# VT6212_Chipset.net
KiCad netlist of a schematic drawn in Altium Designer
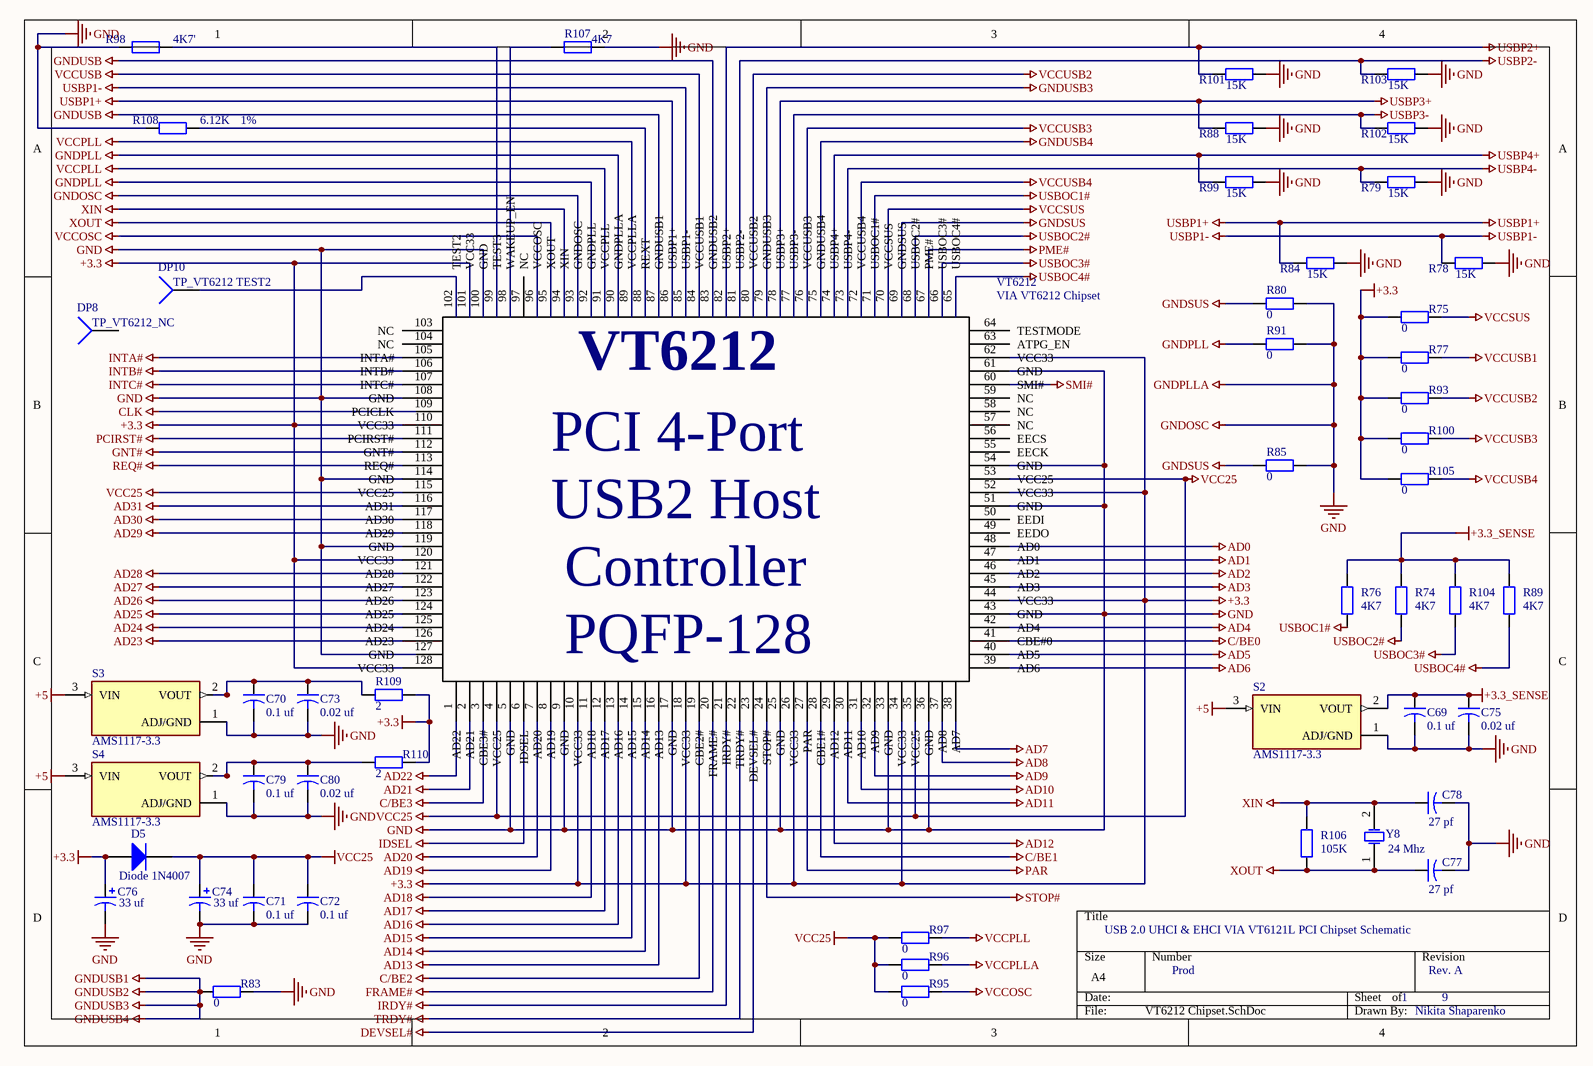
[diagram p0: VT6212 Chipset.SchDoc]

(export (version "E")
  (design (tool "Eeschema 10.0.6"))
  (components
    (comp (ref "C69")
      (value "0.1 uf")
      (footprint "CAPR5-4X5")
      (description "Capacitor")
      (fields (field (name "Comment") "Cap2") (field (name "PUBLISHER") "Altium Limited"))
      (libsource (lib "Miscellaneous Devices") (part "Cap2"))
    )
    (comp (ref "C70")
      (value "0.1 uf")
      (footprint "CAPR5-4X5")
      (description "Capacitor")
      (fields (field (name "Comment") "Cap2") (field (name "PUBLISHER") "Altium Limited"))
      (libsource (lib "Miscellaneous Devices") (part "Cap2"))
    )
    (comp (ref "C71")
      (value "0.1 uf")
      (footprint "CAPR5-4X5")
      (description "Capacitor")
      (fields (field (name "Comment") "Cap2") (field (name "PUBLISHER") "Altium Limited"))
      (libsource (lib "Miscellaneous Devices") (part "Cap2"))
    )
    (comp (ref "C72")
      (value "0.1 uf")
      (footprint "CAPR5-4X5")
      (description "Capacitor")
      (fields (field (name "Comment") "Cap2") (field (name "PUBLISHER") "Altium Limited"))
      (libsource (lib "Miscellaneous Devices") (part "Cap2"))
    )
    (comp (ref "C73")
      (value "0.02 uf")
      (footprint "CAPR5-4X5")
      (description "Capacitor")
      (fields (field (name "Comment") "Cap2") (field (name "PUBLISHER") "Altium Limited"))
      (libsource (lib "Miscellaneous Devices") (part "Cap2"))
    )
    (comp (ref "C74")
      (value "33 uf")
      (footprint "RAD-0.2")
      (description "Polarized Capacitor (Radial)")
      (fields (field (name "Comment") "Cap Pol1") (field (name "PUBLISHER") "Altium Limited"))
      (libsource (lib "Miscellaneous Devices") (part "Cap Pol1"))
    )
    (comp (ref "C75")
      (value "0.02 uf")
      (footprint "CAPR5-4X5")
      (description "Capacitor")
      (fields (field (name "Comment") "Cap2") (field (name "PUBLISHER") "Altium Limited"))
      (libsource (lib "Miscellaneous Devices") (part "Cap2"))
    )
    (comp (ref "C76")
      (value "33 uf")
      (footprint "RAD-0.2")
      (description "Polarized Capacitor (Radial)")
      (fields (field (name "Comment") "Cap Pol1") (field (name "PUBLISHER") "Altium Limited"))
      (libsource (lib "Miscellaneous Devices") (part "Cap Pol1"))
    )
    (comp (ref "C77")
      (value "27 pf")
      (footprint "CAPR5-4X5")
      (description "Capacitor")
      (fields (field (name "Comment") "Cap2") (field (name "PUBLISHER") "Altium Limited"))
      (libsource (lib "Miscellaneous Devices") (part "Cap2"))
    )
    (comp (ref "C78")
      (value "27 pf")
      (footprint "CAPR5-4X5")
      (description "Capacitor")
      (fields (field (name "Comment") "Cap2") (field (name "PUBLISHER") "Altium Limited"))
      (libsource (lib "Miscellaneous Devices") (part "Cap2"))
    )
    (comp (ref "C79")
      (value "0.1 uf")
      (footprint "CAPR5-4X5")
      (description "Capacitor")
      (fields (field (name "Comment") "Cap2") (field (name "PUBLISHER") "Altium Limited"))
      (libsource (lib "Miscellaneous Devices") (part "Cap2"))
    )
    (comp (ref "C80")
      (value "0.02 uf")
      (footprint "CAPR5-4X5")
      (description "Capacitor")
      (fields (field (name "Comment") "Cap2") (field (name "PUBLISHER") "Altium Limited"))
      (libsource (lib "Miscellaneous Devices") (part "Cap2"))
    )
    (comp (ref "D5")
      (value "Diode 1N4007")
      (footprint "DO-41")
      (description "1 Amp General Purpose Rectifier")
      (fields (field (name "PUBLISHER") "Altium Limited"))
      (libsource (lib "Miscellaneous Devices") (part "Diode 1N4007"))
    )
    (comp (ref "DP8")
      (value "TP_VT6212_NC")
      (footprint "PIN1")
      (description "Socket")
      (fields (field (name "PUBLISHER") "Altium Limited"))
      (libsource (lib "Miscellaneous Connectors") (part "Socket"))
    )
    (comp (ref "DP10")
      (value "TP_VT6212 TEST2")
      (footprint "PIN1")
      (description "Socket")
      (fields (field (name "PUBLISHER") "Altium Limited"))
      (libsource (lib "Miscellaneous Connectors") (part "Socket"))
    )
    (comp (ref "R74")
      (value "4K7")
      (footprint "AXIAL-0.4")
      (description "Resistor")
      (fields (field (name "Comment") "Res2") (field (name "PUBLISHER") "Altium Limited"))
      (libsource (lib "") (part "Res2_2"))
    )
    (comp (ref "R75")
      (value "0")
      (footprint "AXIAL-0.4")
      (description "Resistor")
      (fields (field (name "Comment") "Res2") (field (name "PUBLISHER") "Altium Limited"))
      (libsource (lib "Miscellaneous Devices") (part "Res2"))
    )
    (comp (ref "R76")
      (value "4K7")
      (footprint "AXIAL-0.4")
      (description "Resistor")
      (fields (field (name "Comment") "Res2") (field (name "PUBLISHER") "Altium Limited"))
      (libsource (lib "") (part "Res2_2"))
    )
    (comp (ref "R77")
      (value "0")
      (footprint "AXIAL-0.4")
      (description "Resistor")
      (fields (field (name "Comment") "Res2") (field (name "PUBLISHER") "Altium Limited"))
      (libsource (lib "Miscellaneous Devices") (part "Res2"))
    )
    (comp (ref "R78")
      (value "15K")
      (footprint "AXIAL-0.4")
      (description "Resistor")
      (fields (field (name "Comment") "Res2") (field (name "PUBLISHER") "Altium Limited"))
      (libsource (lib "Miscellaneous Devices") (part "Res2"))
    )
    (comp (ref "R79")
      (value "15K")
      (footprint "AXIAL-0.4")
      (description "Resistor")
      (fields (field (name "Comment") "Res2") (field (name "PUBLISHER") "Altium Limited"))
      (libsource (lib "Miscellaneous Devices") (part "Res2"))
    )
    (comp (ref "R80")
      (value "0")
      (footprint "AXIAL-0.4")
      (description "Resistor")
      (fields (field (name "Comment") "Res2") (field (name "PUBLISHER") "Altium Limited"))
      (libsource (lib "") (part "Res2_1"))
    )
    (comp (ref "R83")
      (value "0")
      (footprint "AXIAL-0.4")
      (description "Resistor")
      (fields (field (name "Comment") "Res2") (field (name "PUBLISHER") "Altium Limited"))
      (libsource (lib "Miscellaneous Devices") (part "Res2"))
    )
    (comp (ref "R84")
      (value "15K")
      (footprint "AXIAL-0.4")
      (description "Resistor")
      (fields (field (name "Comment") "Res2") (field (name "PUBLISHER") "Altium Limited"))
      (libsource (lib "Miscellaneous Devices") (part "Res2"))
    )
    (comp (ref "R85")
      (value "0")
      (footprint "AXIAL-0.4")
      (description "Resistor")
      (fields (field (name "Comment") "Res2") (field (name "PUBLISHER") "Altium Limited"))
      (libsource (lib "") (part "Res2_1"))
    )
    (comp (ref "R88")
      (value "15K")
      (footprint "AXIAL-0.4")
      (description "Resistor")
      (fields (field (name "Comment") "Res2") (field (name "PUBLISHER") "Altium Limited"))
      (libsource (lib "Miscellaneous Devices") (part "Res2"))
    )
    (comp (ref "R89")
      (value "4K7")
      (footprint "AXIAL-0.4")
      (description "Resistor")
      (fields (field (name "Comment") "Res2") (field (name "PUBLISHER") "Altium Limited"))
      (libsource (lib "") (part "Res2_2"))
    )
    (comp (ref "R91")
      (value "0")
      (footprint "AXIAL-0.4")
      (description "Resistor")
      (fields (field (name "Comment") "Res2") (field (name "PUBLISHER") "Altium Limited"))
      (libsource (lib "") (part "Res2_1"))
    )
    (comp (ref "R93")
      (value "0")
      (footprint "AXIAL-0.4")
      (description "Resistor")
      (fields (field (name "Comment") "Res2") (field (name "PUBLISHER") "Altium Limited"))
      (libsource (lib "Miscellaneous Devices") (part "Res2"))
    )
    (comp (ref "R95")
      (value "0")
      (footprint "AXIAL-0.4")
      (description "Resistor")
      (fields (field (name "Comment") "Res2") (field (name "PUBLISHER") "Altium Limited"))
      (libsource (lib "Miscellaneous Devices") (part "Res2"))
    )
    (comp (ref "R96")
      (value "0")
      (footprint "AXIAL-0.4")
      (description "Resistor")
      (fields (field (name "Comment") "Res2") (field (name "PUBLISHER") "Altium Limited"))
      (libsource (lib "Miscellaneous Devices") (part "Res2"))
    )
    (comp (ref "R97")
      (value "0")
      (footprint "AXIAL-0.4")
      (description "Resistor")
      (fields (field (name "Comment") "Res2") (field (name "PUBLISHER") "Altium Limited"))
      (libsource (lib "Miscellaneous Devices") (part "Res2"))
    )
    (comp (ref "R98")
      (value "4K7'")
      (footprint "AXIAL-0.4")
      (description "Resistor")
      (fields (field (name "PUBLISHER") "Altium Limited"))
      (libsource (lib "") (part "Res2_1"))
    )
    (comp (ref "R99")
      (value "15K")
      (footprint "AXIAL-0.4")
      (description "Resistor")
      (fields (field (name "Comment") "Res2") (field (name "PUBLISHER") "Altium Limited"))
      (libsource (lib "Miscellaneous Devices") (part "Res2"))
    )
    (comp (ref "R100")
      (value "0")
      (footprint "AXIAL-0.4")
      (description "Resistor")
      (fields (field (name "Comment") "Res2") (field (name "PUBLISHER") "Altium Limited"))
      (libsource (lib "Miscellaneous Devices") (part "Res2"))
    )
    (comp (ref "R101")
      (value "15K")
      (footprint "AXIAL-0.4")
      (description "Resistor")
      (fields (field (name "Comment") "Res2") (field (name "PUBLISHER") "Altium Limited"))
      (libsource (lib "Miscellaneous Devices") (part "Res2"))
    )
    (comp (ref "R102")
      (value "15K")
      (footprint "AXIAL-0.4")
      (description "Resistor")
      (fields (field (name "Comment") "Res2") (field (name "PUBLISHER") "Altium Limited"))
      (libsource (lib "Miscellaneous Devices") (part "Res2"))
    )
    (comp (ref "R103")
      (value "15K")
      (footprint "AXIAL-0.4")
      (description "Resistor")
      (fields (field (name "Comment") "Res2") (field (name "PUBLISHER") "Altium Limited"))
      (libsource (lib "Miscellaneous Devices") (part "Res2"))
    )
    (comp (ref "R104")
      (value "4K7")
      (footprint "AXIAL-0.4")
      (description "Resistor")
      (fields (field (name "Comment") "Res2") (field (name "PUBLISHER") "Altium Limited"))
      (libsource (lib "") (part "Res2_2"))
    )
    (comp (ref "R105")
      (value "0")
      (footprint "AXIAL-0.4")
      (description "Resistor")
      (fields (field (name "Comment") "Res2") (field (name "PUBLISHER") "Altium Limited"))
      (libsource (lib "Miscellaneous Devices") (part "Res2"))
    )
    (comp (ref "R106")
      (value "105K")
      (footprint "AXIAL-0.4")
      (description "Resistor")
      (fields (field (name "Comment") "Res2") (field (name "PUBLISHER") "Altium Limited"))
      (libsource (lib "") (part "Res2_2"))
    )
    (comp (ref "R107")
      (value "4K7")
      (footprint "AXIAL-0.4")
      (description "Resistor")
      (fields (field (name "Comment") "Res2") (field (name "PUBLISHER") "Altium Limited"))
      (libsource (lib "Miscellaneous Devices") (part "Res2"))
    )
    (comp (ref "R108")
      (value "1%")
      (footprint "AXIAL-0.4")
      (description "Resistor")
      (fields (field (name "ALTIUM_VALUE") "6.12K") (field (name "PUBLISHER") "Altium Limited"))
      (libsource (lib "") (part "Res2_1"))
    )
    (comp (ref "R109")
      (value "2")
      (footprint "AXIAL-0.4")
      (description "Resistor")
      (fields (field (name "Comment") "Res2") (field (name "PUBLISHER") "Altium Limited"))
      (libsource (lib "") (part "Res2_1"))
    )
    (comp (ref "R110")
      (value "2")
      (footprint "AXIAL-0.4")
      (description "Resistor")
      (fields (field (name "Comment") "Res2") (field (name "PUBLISHER") "Altium Limited"))
      (libsource (lib "Miscellaneous Devices") (part "Res2"))
    )
    (comp (ref "S2")
      (value "AMS1117-3.3")
      (footprint "SOT229P700X180-4N")
      (description "Sot223/Pkg 1-Amp 3.3-Volt Low Drop Out Voltage Regulatator")
      (fields (field (name "MF") "Advanced Monolithic Systems"))
      (libsource (lib "AMS1117-3.3") (part "AMS1117-3.3"))
    )
    (comp (ref "S3")
      (value "AMS1117-3.3")
      (footprint "SOT229P700X180-4N")
      (description "Sot223/Pkg 1-Amp 3.3-Volt Low Drop Out Voltage Regulatator")
      (fields (field (name "MF") "Advanced Monolithic Systems"))
      (libsource (lib "AMS1117-3.3") (part "AMS1117-3.3"))
    )
    (comp (ref "S4")
      (value "AMS1117-3.3")
      (footprint "SOT229P700X180-4N")
      (description "Sot223/Pkg 1-Amp 3.3-Volt Low Drop Out Voltage Regulatator")
      (fields (field (name "MF") "Advanced Monolithic Systems"))
      (libsource (lib "AMS1117-3.3") (part "AMS1117-3.3"))
    )
    (comp (ref "VT6212")
      (value "VIA VT6212 Chipset")
      (footprint "NXP LQFP-144 SOT486-1")
      (description "VT6212 PCI 4-Port USB2 Host Controller PQFP-128")
      (libsource (lib "VIA VT6212") (part "VT6212"))
    )
    (comp (ref "Y8")
      (value "24 Mhz")
      (footprint "R38")
      (description "Crystal Oscillator")
      (fields (field (name "PUBLISHER") "Altium Limited"))
      (libsource (lib "Miscellaneous Devices") (part "XTAL"))
    )
  )
  (nets
    (net (code "1") (name "+3.3") (class "Default")
      (node (ref "C76") (pin "1") (pinfunction "1_1") (pintype "passive"))
      (node (ref "D5") (pin "1") (pinfunction "A_1") (pintype "passive"))
      (node (ref "R100") (pin "2") (pinfunction "2_2") (pintype "passive"))
      (node (ref "R105") (pin "2") (pinfunction "2_2") (pintype "passive"))
      (node (ref "R109") (pin "2") (pinfunction "2_2") (pintype "passive"))
      (node (ref "R110") (pin "1") (pinfunction "1_1") (pintype "passive"))
      (node (ref "R75") (pin "2") (pinfunction "2_2") (pintype "passive"))
      (node (ref "R77") (pin "2") (pinfunction "2_2") (pintype "passive"))
      (node (ref "R93") (pin "2") (pinfunction "2_2") (pintype "passive"))
      (node (ref "VT6212") (pin "101") (pinfunction "VCC33_101") (pintype "passive"))
    )
    (net (code "2") (name "+3.3_SENSE") (class "Default")
      (node (ref "C69") (pin "1") (pinfunction "1_1") (pintype "passive"))
      (node (ref "C75") (pin "1") (pinfunction "1_1") (pintype "passive"))
      (node (ref "R104") (pin "2") (pinfunction "2_2") (pintype "passive"))
      (node (ref "R74") (pin "2") (pinfunction "2_2") (pintype "passive"))
      (node (ref "R76") (pin "2") (pinfunction "2_2") (pintype "passive"))
      (node (ref "R89") (pin "2") (pinfunction "2_2") (pintype "passive"))
      (node (ref "S2") (pin "2") (pinfunction "VOUT_2") (pintype "output"))
    )
    (net (code "3") (name "+5") (class "Default")
      (node (ref "S2") (pin "3") (pinfunction "VIN_3") (pintype "input"))
      (node (ref "S3") (pin "3") (pinfunction "VIN_3") (pintype "input"))
      (node (ref "S4") (pin "3") (pinfunction "VIN_3") (pintype "input"))
    )
    (net (code "43") (name "GND") (class "Default")
      (node (ref "C69") (pin "2") (pinfunction "2_2") (pintype "passive"))
      (node (ref "C70") (pin "2") (pinfunction "2_2") (pintype "passive"))
      (node (ref "C71") (pin "2") (pinfunction "2_2") (pintype "passive"))
      (node (ref "C72") (pin "2") (pinfunction "2_2") (pintype "passive"))
      (node (ref "C73") (pin "2") (pinfunction "2_2") (pintype "passive"))
      (node (ref "C74") (pin "2") (pinfunction "2_2") (pintype "passive"))
      (node (ref "C75") (pin "2") (pinfunction "2_2") (pintype "passive"))
      (node (ref "C76") (pin "2") (pinfunction "2_2") (pintype "passive"))
      (node (ref "C77") (pin "2") (pinfunction "2_2") (pintype "passive"))
      (node (ref "C78") (pin "2") (pinfunction "2_2") (pintype "passive"))
      (node (ref "C79") (pin "2") (pinfunction "2_2") (pintype "passive"))
      (node (ref "C80") (pin "2") (pinfunction "2_2") (pintype "passive"))
      (node (ref "R101") (pin "1") (pinfunction "1_1") (pintype "passive"))
      (node (ref "R102") (pin "1") (pinfunction "1_1") (pintype "passive"))
      (node (ref "R103") (pin "1") (pinfunction "1_1") (pintype "passive"))
      (node (ref "R107") (pin "1") (pinfunction "1_1") (pintype "passive"))
      (node (ref "R108") (pin "1") (pinfunction "1_1") (pintype "passive"))
      (node (ref "R78") (pin "1") (pinfunction "1_1") (pintype "passive"))
      (node (ref "R79") (pin "1") (pinfunction "1_1") (pintype "passive"))
      (node (ref "R80") (pin "2") (pinfunction "2_2") (pintype "passive"))
      (node (ref "R83") (pin "1") (pinfunction "1_1") (pintype "passive"))
      (node (ref "R84") (pin "1") (pinfunction "1_1") (pintype "passive"))
      (node (ref "R85") (pin "2") (pinfunction "2_2") (pintype "passive"))
      (node (ref "R88") (pin "1") (pinfunction "1_1") (pintype "passive"))
      (node (ref "R91") (pin "2") (pinfunction "2_2") (pintype "passive"))
      (node (ref "R98") (pin "1") (pinfunction "1_1") (pintype "passive"))
      (node (ref "R99") (pin "1") (pinfunction "1_1") (pintype "passive"))
      (node (ref "S2") (pin "1") (pinfunction "ADJ/GND_1") (pintype "power_in"))
      (node (ref "S3") (pin "1") (pinfunction "ADJ/GND_1") (pintype "power_in"))
      (node (ref "S4") (pin "1") (pinfunction "ADJ/GND_1") (pintype "power_in"))
      (node (ref "VT6212") (pin "100") (pinfunction "GND_100") (pintype "passive"))
      (node (ref "VT6212") (pin "93") (pinfunction "GNDOSC_93") (pintype "passive"))
    )
    (net (code "44") (name "GNDPLL") (class "Default")
      (node (ref "R91") (pin "1") (pinfunction "1_1") (pintype "passive"))
      (node (ref "VT6212") (pin "90") (pinfunction "GNDPLLA_90") (pintype "passive"))
      (node (ref "VT6212") (pin "92") (pinfunction "GNDPLL_92") (pintype "passive"))
    )
    (net (code "45") (name "GNDSUS") (class "Default")
      (node (ref "R80") (pin "1") (pinfunction "1_1") (pintype "passive"))
      (node (ref "R85") (pin "1") (pinfunction "1_1") (pintype "passive"))
      (node (ref "VT6212") (pin "69") (pinfunction "GNDSUS_69") (pintype "passive"))
    )
    (net (code "46") (name "GNDUSB") (class "Default")
      (node (ref "VT6212") (pin "83") (pinfunction "GNDUSB2_83") (pintype "passive"))
      (node (ref "VT6212") (pin "87") (pinfunction "GNDUSB1_87") (pintype "passive"))
    )
    (net (code "47") (name "GNDUSB1") (class "Default")
      (node (ref "R83") (pin "2") (pinfunction "2_2") (pintype "passive"))
      (node (ref "VT6212") (pin "75") (pinfunction "GNDUSB4_75") (pintype "passive"))
      (node (ref "VT6212") (pin "79") (pinfunction "GNDUSB3_79") (pintype "passive"))
    )
    (net (code "54") (name "Net-(S3-VOUT)") (class "Default")
      (node (ref "C70") (pin "1") (pinfunction "1_1") (pintype "passive"))
      (node (ref "C73") (pin "1") (pinfunction "1_1") (pintype "passive"))
      (node (ref "R109") (pin "1") (pinfunction "1_1") (pintype "passive"))
      (node (ref "S3") (pin "2") (pinfunction "VOUT_2") (pintype "output"))
    )
    (net (code "55") (name "Net-(S4-VOUT)") (class "Default")
      (node (ref "C79") (pin "1") (pinfunction "1_1") (pintype "passive"))
      (node (ref "C80") (pin "1") (pinfunction "1_1") (pintype "passive"))
      (node (ref "R110") (pin "2") (pinfunction "2_2") (pintype "passive"))
      (node (ref "S4") (pin "2") (pinfunction "VOUT_2") (pintype "output"))
    )
    (net (code "56") (name "Net-(VT6212-REXT)") (class "Default")
      (node (ref "R108") (pin "2") (pinfunction "2_2") (pintype "passive"))
      (node (ref "VT6212") (pin "88") (pinfunction "REXT_88") (pintype "passive"))
    )
    (net (code "57") (name "Net-(VT6212-TEST2)") (class "Default")
      (node (ref "DP10") (pin "1") (pinfunction "1_1") (pintype "passive"))
      (node (ref "VT6212") (pin "102") (pinfunction "TEST2_102") (pintype "passive"))
    )
    (net (code "58") (name "Net-(VT6212-TEST3)") (class "Default")
      (node (ref "R98") (pin "2") (pinfunction "2_2") (pintype "passive"))
      (node (ref "VT6212") (pin "99") (pinfunction "TEST3_99") (pintype "passive"))
    )
    (net (code "59") (name "Net-(VT6212-WAKEUP_EN)") (class "Default")
      (node (ref "R107") (pin "2") (pinfunction "2_2") (pintype "passive"))
      (node (ref "VT6212") (pin "98") (pinfunction "WAKEUP_EN_98") (pintype "passive"))
    )
    (net (code "62") (name "PME#") (class "Default")
      (node (ref "VT6212") (pin "67") (pinfunction "PME#_67") (pintype "passive"))
    )
    (net (code "67") (name "USBOC1#") (class "Default")
      (node (ref "R76") (pin "1") (pinfunction "1_1") (pintype "passive"))
      (node (ref "VT6212") (pin "71") (pinfunction "USBOC1#_71") (pintype "passive"))
    )
    (net (code "68") (name "USBOC2#") (class "Default")
      (node (ref "R74") (pin "1") (pinfunction "1_1") (pintype "passive"))
      (node (ref "VT6212") (pin "68") (pinfunction "USBOC2#_68") (pintype "passive"))
    )
    (net (code "69") (name "USBOC3#") (class "Default")
      (node (ref "R104") (pin "1") (pinfunction "1_1") (pintype "passive"))
      (node (ref "VT6212") (pin "66") (pinfunction "USBOC3#_66") (pintype "passive"))
    )
    (net (code "70") (name "USBOC4#") (class "Default")
      (node (ref "R89") (pin "1") (pinfunction "1_1") (pintype "passive"))
      (node (ref "VT6212") (pin "65") (pinfunction "USBOC4#_65") (pintype "passive"))
    )
    (net (code "71") (name "USBP1+") (class "Default")
      (node (ref "R84") (pin "2") (pinfunction "2_2") (pintype "passive"))
      (node (ref "VT6212") (pin "86") (pinfunction "USBP1+_86") (pintype "passive"))
    )
    (net (code "72") (name "USBP1-") (class "Default")
      (node (ref "R78") (pin "2") (pinfunction "2_2") (pintype "passive"))
      (node (ref "VT6212") (pin "85") (pinfunction "USBP1-_85") (pintype "passive"))
    )
    (net (code "73") (name "USBP2+") (class "Default")
      (node (ref "R101") (pin "2") (pinfunction "2_2") (pintype "passive"))
      (node (ref "VT6212") (pin "82") (pinfunction "USBP2+_82") (pintype "passive"))
    )
    (net (code "74") (name "USBP2-") (class "Default")
      (node (ref "R103") (pin "2") (pinfunction "2_2") (pintype "passive"))
      (node (ref "VT6212") (pin "81") (pinfunction "USBP2-_81") (pintype "passive"))
    )
    (net (code "75") (name "USBP3+") (class "Default")
      (node (ref "R88") (pin "2") (pinfunction "2_2") (pintype "passive"))
      (node (ref "VT6212") (pin "78") (pinfunction "USBP3+_78") (pintype "passive"))
    )
    (net (code "76") (name "USBP3-") (class "Default")
      (node (ref "R102") (pin "2") (pinfunction "2_2") (pintype "passive"))
      (node (ref "VT6212") (pin "77") (pinfunction "USBP3-_77") (pintype "passive"))
    )
    (net (code "77") (name "USBP4+") (class "Default")
      (node (ref "R99") (pin "2") (pinfunction "2_2") (pintype "passive"))
      (node (ref "VT6212") (pin "74") (pinfunction "USBP4+_74") (pintype "passive"))
    )
    (net (code "78") (name "USBP4-") (class "Default")
      (node (ref "R79") (pin "2") (pinfunction "2_2") (pintype "passive"))
      (node (ref "VT6212") (pin "73") (pinfunction "USBP4-_73") (pintype "passive"))
    )
    (net (code "79") (name "VCC25") (class "Default")
      (node (ref "C71") (pin "1") (pinfunction "1_1") (pintype "passive"))
      (node (ref "C72") (pin "1") (pinfunction "1_1") (pintype "passive"))
      (node (ref "C74") (pin "1") (pinfunction "1_1") (pintype "passive"))
      (node (ref "D5") (pin "2") (pinfunction "K_2") (pintype "passive"))
      (node (ref "R95") (pin "2") (pinfunction "2_2") (pintype "passive"))
      (node (ref "R96") (pin "2") (pinfunction "2_2") (pintype "passive"))
      (node (ref "R97") (pin "2") (pinfunction "2_2") (pintype "passive"))
    )
    (net (code "80") (name "VCCOSC") (class "Default")
      (node (ref "R95") (pin "1") (pinfunction "1_1") (pintype "passive"))
      (node (ref "VT6212") (pin "96") (pinfunction "VCCOSC_96") (pintype "passive"))
    )
    (net (code "81") (name "VCCPLL") (class "Default")
      (node (ref "R97") (pin "1") (pinfunction "1_1") (pintype "passive"))
      (node (ref "VT6212") (pin "89") (pinfunction "VCCPLLA_89") (pintype "passive"))
      (node (ref "VT6212") (pin "91") (pinfunction "VCCPLL_91") (pintype "passive"))
    )
    (net (code "82") (name "VCCPLLA") (class "Default")
      (node (ref "R96") (pin "1") (pinfunction "1_1") (pintype "passive"))
    )
    (net (code "83") (name "VCCSUS") (class "Default")
      (node (ref "R75") (pin "1") (pinfunction "1_1") (pintype "passive"))
      (node (ref "VT6212") (pin "70") (pinfunction "VCCSUS_70") (pintype "passive"))
    )
    (net (code "84") (name "VCCUSB") (class "Default")
      (node (ref "VT6212") (pin "84") (pinfunction "VCCUSB1_84") (pintype "passive"))
    )
    (net (code "85") (name "VCCUSB1") (class "Default")
      (node (ref "R77") (pin "1") (pinfunction "1_1") (pintype "passive"))
    )
    (net (code "86") (name "VCCUSB2") (class "Default")
      (node (ref "R93") (pin "1") (pinfunction "1_1") (pintype "passive"))
      (node (ref "VT6212") (pin "80") (pinfunction "VCCUSB2_80") (pintype "passive"))
    )
    (net (code "87") (name "VCCUSB3") (class "Default")
      (node (ref "R100") (pin "1") (pinfunction "1_1") (pintype "passive"))
      (node (ref "VT6212") (pin "76") (pinfunction "VCCUSB3_76") (pintype "passive"))
    )
    (net (code "88") (name "VCCUSB4") (class "Default")
      (node (ref "R105") (pin "1") (pinfunction "1_1") (pintype "passive"))
      (node (ref "VT6212") (pin "72") (pinfunction "VCCUSB4_72") (pintype "passive"))
    )
    (net (code "89") (name "XIN") (class "Default")
      (node (ref "C78") (pin "1") (pinfunction "1_1") (pintype "passive"))
      (node (ref "R106") (pin "2") (pinfunction "2_2") (pintype "passive"))
      (node (ref "VT6212") (pin "94") (pinfunction "XIN_94") (pintype "passive"))
      (node (ref "Y8") (pin "2") (pinfunction "OSC2_2") (pintype "passive"))
    )
    (net (code "90") (name "XOUT") (class "Default")
      (node (ref "C77") (pin "1") (pinfunction "1_1") (pintype "passive"))
      (node (ref "R106") (pin "1") (pinfunction "1_1") (pintype "passive"))
      (node (ref "VT6212") (pin "95") (pinfunction "XOUT_95") (pintype "passive"))
      (node (ref "Y8") (pin "1") (pinfunction "OSC1_1") (pintype "passive"))
    )
    (net (code "91") (name "unconnected-(DP8-Pad1)") (class "Default")
      (node (ref "DP8") (pin "1") (pinfunction "1_1") (pintype "passive"))
    )
    (net (code "92") (name "unconnected-(VT6212-AD0-Pad48)") (class "Default")
      (node (ref "VT6212") (pin "48") (pinfunction "AD0_48") (pintype "passive"))
    )
    (net (code "93") (name "unconnected-(VT6212-AD1-Pad47)") (class "Default")
      (node (ref "VT6212") (pin "47") (pinfunction "AD1_47") (pintype "passive"))
    )
    (net (code "94") (name "unconnected-(VT6212-AD2-Pad46)") (class "Default")
      (node (ref "VT6212") (pin "46") (pinfunction "AD2_46") (pintype "passive"))
    )
    (net (code "95") (name "unconnected-(VT6212-AD3-Pad45)") (class "Default")
      (node (ref "VT6212") (pin "45") (pinfunction "AD3_45") (pintype "passive"))
    )
    (net (code "96") (name "unconnected-(VT6212-AD4-Pad42)") (class "Default")
      (node (ref "VT6212") (pin "42") (pinfunction "AD4_42") (pintype "passive"))
    )
    (net (code "97") (name "unconnected-(VT6212-AD5-Pad40)") (class "Default")
      (node (ref "VT6212") (pin "40") (pinfunction "AD5_40") (pintype "passive"))
    )
    (net (code "98") (name "unconnected-(VT6212-AD6-Pad39)") (class "Default")
      (node (ref "VT6212") (pin "39") (pinfunction "AD6_39") (pintype "passive"))
    )
    (net (code "99") (name "unconnected-(VT6212-AD7-Pad38)") (class "Default")
      (node (ref "VT6212") (pin "38") (pinfunction "AD7_38") (pintype "passive"))
    )
    (net (code "100") (name "unconnected-(VT6212-AD8-Pad37)") (class "Default")
      (node (ref "VT6212") (pin "37") (pinfunction "AD8_37") (pintype "passive"))
    )
    (net (code "101") (name "unconnected-(VT6212-AD9-Pad32)") (class "Default")
      (node (ref "VT6212") (pin "32") (pinfunction "AD9_32") (pintype "passive"))
    )
    (net (code "102") (name "unconnected-(VT6212-AD10-Pad31)") (class "Default")
      (node (ref "VT6212") (pin "31") (pinfunction "AD10_31") (pintype "passive"))
    )
    (net (code "103") (name "unconnected-(VT6212-AD11-Pad30)") (class "Default")
      (node (ref "VT6212") (pin "30") (pinfunction "AD11_30") (pintype "passive"))
    )
    (net (code "104") (name "unconnected-(VT6212-AD12-Pad29)") (class "Default")
      (node (ref "VT6212") (pin "29") (pinfunction "AD12_29") (pintype "passive"))
    )
    (net (code "105") (name "unconnected-(VT6212-AD13-Pad16)") (class "Default")
      (node (ref "VT6212") (pin "16") (pinfunction "AD13_16") (pintype "passive"))
    )
    (net (code "106") (name "unconnected-(VT6212-AD14-Pad15)") (class "Default")
      (node (ref "VT6212") (pin "15") (pinfunction "AD14_15") (pintype "passive"))
    )
    (net (code "107") (name "unconnected-(VT6212-AD15-Pad14)") (class "Default")
      (node (ref "VT6212") (pin "14") (pinfunction "AD15_14") (pintype "passive"))
    )
    (net (code "108") (name "unconnected-(VT6212-AD16-Pad13)") (class "Default")
      (node (ref "VT6212") (pin "13") (pinfunction "AD16_13") (pintype "passive"))
    )
    (net (code "109") (name "unconnected-(VT6212-AD17-Pad12)") (class "Default")
      (node (ref "VT6212") (pin "12") (pinfunction "AD17_12") (pintype "passive"))
    )
    (net (code "110") (name "unconnected-(VT6212-AD18-Pad11)") (class "Default")
      (node (ref "VT6212") (pin "11") (pinfunction "AD18_11") (pintype "passive"))
    )
    (net (code "111") (name "unconnected-(VT6212-AD19-Pad8)") (class "Default")
      (node (ref "VT6212") (pin "8") (pinfunction "AD19_8") (pintype "passive"))
    )
    (net (code "112") (name "unconnected-(VT6212-AD20-Pad7)") (class "Default")
      (node (ref "VT6212") (pin "7") (pinfunction "AD20_7") (pintype "passive"))
    )
    (net (code "113") (name "unconnected-(VT6212-AD21-Pad2)") (class "Default")
      (node (ref "VT6212") (pin "2") (pinfunction "AD21_2") (pintype "passive"))
    )
    (net (code "114") (name "unconnected-(VT6212-AD22-Pad1)") (class "Default")
      (node (ref "VT6212") (pin "1") (pinfunction "AD22_1") (pintype "passive"))
    )
    (net (code "115") (name "unconnected-(VT6212-AD23-Pad126)") (class "Default")
      (node (ref "VT6212") (pin "126") (pinfunction "AD23_126") (pintype "passive"))
    )
    (net (code "116") (name "unconnected-(VT6212-AD24-Pad125)") (class "Default")
      (node (ref "VT6212") (pin "125") (pinfunction "AD24_125") (pintype "passive"))
    )
    (net (code "117") (name "unconnected-(VT6212-AD25-Pad124)") (class "Default")
      (node (ref "VT6212") (pin "124") (pinfunction "AD25_124") (pintype "passive"))
    )
    (net (code "118") (name "unconnected-(VT6212-AD26-Pad123)") (class "Default")
      (node (ref "VT6212") (pin "123") (pinfunction "AD26_123") (pintype "passive"))
    )
    (net (code "119") (name "unconnected-(VT6212-AD27-Pad122)") (class "Default")
      (node (ref "VT6212") (pin "122") (pinfunction "AD27_122") (pintype "passive"))
    )
    (net (code "120") (name "unconnected-(VT6212-AD28-Pad121)") (class "Default")
      (node (ref "VT6212") (pin "121") (pinfunction "AD28_121") (pintype "passive"))
    )
    (net (code "121") (name "unconnected-(VT6212-AD29-Pad118)") (class "Default")
      (node (ref "VT6212") (pin "118") (pinfunction "AD29_118") (pintype "passive"))
    )
    (net (code "122") (name "unconnected-(VT6212-AD30-Pad117)") (class "Default")
      (node (ref "VT6212") (pin "117") (pinfunction "AD30_117") (pintype "passive"))
    )
    (net (code "123") (name "unconnected-(VT6212-AD31-Pad116)") (class "Default")
      (node (ref "VT6212") (pin "116") (pinfunction "AD31_116") (pintype "passive"))
    )
    (net (code "124") (name "unconnected-(VT6212-ATPG_EN-Pad63)") (class "Default")
      (node (ref "VT6212") (pin "63") (pinfunction "ATPG_EN_63") (pintype "passive"))
    )
    (net (code "125") (name "unconnected-(VT6212-CBE#0-Pad41)") (class "Default")
      (node (ref "VT6212") (pin "41") (pinfunction "CBE#0_41") (pintype "passive"))
    )
    (net (code "126") (name "unconnected-(VT6212-CBE1#-Pad28)") (class "Default")
      (node (ref "VT6212") (pin "28") (pinfunction "CBE1#_28") (pintype "passive"))
    )
    (net (code "127") (name "unconnected-(VT6212-CBE2#-Pad19)") (class "Default")
      (node (ref "VT6212") (pin "19") (pinfunction "CBE2#_19") (pintype "passive"))
    )
    (net (code "128") (name "unconnected-(VT6212-CBE3#-Pad3)") (class "Default")
      (node (ref "VT6212") (pin "3") (pinfunction "CBE3#_3") (pintype "passive"))
    )
    (net (code "129") (name "unconnected-(VT6212-DEVSEL#-Pad23)") (class "Default")
      (node (ref "VT6212") (pin "23") (pinfunction "DEVSEL#_23") (pintype "passive"))
    )
    (net (code "130") (name "unconnected-(VT6212-EECK-Pad55)") (class "Default")
      (node (ref "VT6212") (pin "55") (pinfunction "EECK_55") (pintype "passive"))
    )
    (net (code "131") (name "unconnected-(VT6212-EECS-Pad56)") (class "Default")
      (node (ref "VT6212") (pin "56") (pinfunction "EECS_56") (pintype "passive"))
    )
    (net (code "132") (name "unconnected-(VT6212-EEDI-Pad50)") (class "Default")
      (node (ref "VT6212") (pin "50") (pinfunction "EEDI_50") (pintype "passive"))
    )
    (net (code "133") (name "unconnected-(VT6212-EEDO-Pad49)") (class "Default")
      (node (ref "VT6212") (pin "49") (pinfunction "EEDO_49") (pintype "passive"))
    )
    (net (code "134") (name "unconnected-(VT6212-FRAME#-Pad20)") (class "Default")
      (node (ref "VT6212") (pin "20") (pinfunction "FRAME#_20") (pintype "passive"))
    )
    (net (code "135") (name "unconnected-(VT6212-GND-Pad5)") (class "Default")
      (node (ref "VT6212") (pin "5") (pinfunction "GND_5") (pintype "passive"))
    )
    (net (code "136") (name "unconnected-(VT6212-GND-Pad9)") (class "Default")
      (node (ref "VT6212") (pin "9") (pinfunction "GND_9") (pintype "passive"))
    )
    (net (code "137") (name "unconnected-(VT6212-GND-Pad17)") (class "Default")
      (node (ref "VT6212") (pin "17") (pinfunction "GND_17") (pintype "passive"))
    )
    (net (code "138") (name "unconnected-(VT6212-GND-Pad25)") (class "Default")
      (node (ref "VT6212") (pin "25") (pinfunction "GND_25") (pintype "passive"))
    )
    (net (code "139") (name "unconnected-(VT6212-GND-Pad33)") (class "Default")
      (node (ref "VT6212") (pin "33") (pinfunction "GND_33") (pintype "passive"))
    )
    (net (code "140") (name "unconnected-(VT6212-GND-Pad36)") (class "Default")
      (node (ref "VT6212") (pin "36") (pinfunction "GND_36") (pintype "passive"))
    )
    (net (code "141") (name "unconnected-(VT6212-GND-Pad43)") (class "Default")
      (node (ref "VT6212") (pin "43") (pinfunction "GND_43") (pintype "passive"))
    )
    (net (code "142") (name "unconnected-(VT6212-GND-Pad51)") (class "Default")
      (node (ref "VT6212") (pin "51") (pinfunction "GND_51") (pintype "passive"))
    )
    (net (code "143") (name "unconnected-(VT6212-GND-Pad54)") (class "Default")
      (node (ref "VT6212") (pin "54") (pinfunction "GND_54") (pintype "passive"))
    )
    (net (code "144") (name "unconnected-(VT6212-GND-Pad61)") (class "Default")
      (node (ref "VT6212") (pin "61") (pinfunction "GND_61") (pintype "passive"))
    )
    (net (code "145") (name "unconnected-(VT6212-GND-Pad108)") (class "Default")
      (node (ref "VT6212") (pin "108") (pinfunction "GND_108") (pintype "passive"))
    )
    (net (code "146") (name "unconnected-(VT6212-GND-Pad114)") (class "Default")
      (node (ref "VT6212") (pin "114") (pinfunction "GND_114") (pintype "passive"))
    )
    (net (code "147") (name "unconnected-(VT6212-GND-Pad119)") (class "Default")
      (node (ref "VT6212") (pin "119") (pinfunction "GND_119") (pintype "passive"))
    )
    (net (code "148") (name "unconnected-(VT6212-GND-Pad127)") (class "Default")
      (node (ref "VT6212") (pin "127") (pinfunction "GND_127") (pintype "passive"))
    )
    (net (code "149") (name "unconnected-(VT6212-GNT#-Pad112)") (class "Default")
      (node (ref "VT6212") (pin "112") (pinfunction "GNT#_112") (pintype "passive"))
    )
    (net (code "150") (name "unconnected-(VT6212-IDSEL-Pad6)") (class "Default")
      (node (ref "VT6212") (pin "6") (pinfunction "IDSEL_6") (pintype "passive"))
    )
    (net (code "151") (name "unconnected-(VT6212-INTA#-Pad105)") (class "Default")
      (node (ref "VT6212") (pin "105") (pinfunction "INTA#_105") (pintype "passive"))
    )
    (net (code "152") (name "unconnected-(VT6212-INTB#-Pad106)") (class "Default")
      (node (ref "VT6212") (pin "106") (pinfunction "INTB#_106") (pintype "passive"))
    )
    (net (code "153") (name "unconnected-(VT6212-INTC#-Pad107)") (class "Default")
      (node (ref "VT6212") (pin "107") (pinfunction "INTC#_107") (pintype "passive"))
    )
    (net (code "154") (name "unconnected-(VT6212-IRDY#-Pad21)") (class "Default")
      (node (ref "VT6212") (pin "21") (pinfunction "IRDY#_21") (pintype "passive"))
    )
    (net (code "155") (name "unconnected-(VT6212-NC-Pad57)") (class "Default")
      (node (ref "VT6212") (pin "57") (pinfunction "NC_57") (pintype "passive"))
    )
    (net (code "156") (name "unconnected-(VT6212-NC-Pad58)") (class "Default")
      (node (ref "VT6212") (pin "58") (pinfunction "NC_58") (pintype "passive"))
    )
    (net (code "157") (name "unconnected-(VT6212-NC-Pad59)") (class "Default")
      (node (ref "VT6212") (pin "59") (pinfunction "NC_59") (pintype "passive"))
    )
    (net (code "158") (name "unconnected-(VT6212-NC-Pad97)") (class "Default")
      (node (ref "VT6212") (pin "97") (pinfunction "NC_97") (pintype "passive"))
    )
    (net (code "159") (name "unconnected-(VT6212-NC-Pad103)") (class "Default")
      (node (ref "VT6212") (pin "103") (pinfunction "NC_103") (pintype "passive"))
    )
    (net (code "160") (name "unconnected-(VT6212-NC-Pad104)") (class "Default")
      (node (ref "VT6212") (pin "104") (pinfunction "NC_104") (pintype "passive"))
    )
    (net (code "161") (name "unconnected-(VT6212-PAR-Pad27)") (class "Default")
      (node (ref "VT6212") (pin "27") (pinfunction "PAR_27") (pintype "passive"))
    )
    (net (code "162") (name "unconnected-(VT6212-PCICLK-Pad109)") (class "Default")
      (node (ref "VT6212") (pin "109") (pinfunction "PCICLK_109") (pintype "passive"))
    )
    (net (code "163") (name "unconnected-(VT6212-PCIRST#-Pad111)") (class "Default")
      (node (ref "VT6212") (pin "111") (pinfunction "PCIRST#_111") (pintype "passive"))
    )
    (net (code "164") (name "unconnected-(VT6212-REQ#-Pad113)") (class "Default")
      (node (ref "VT6212") (pin "113") (pinfunction "REQ#_113") (pintype "passive"))
    )
    (net (code "165") (name "unconnected-(VT6212-SMI#-Pad60)") (class "Default")
      (node (ref "VT6212") (pin "60") (pinfunction "SMI#_60") (pintype "passive"))
    )
    (net (code "166") (name "unconnected-(VT6212-STOP#-Pad24)") (class "Default")
      (node (ref "VT6212") (pin "24") (pinfunction "STOP#_24") (pintype "passive"))
    )
    (net (code "167") (name "unconnected-(VT6212-TESTMODE-Pad64)") (class "Default")
      (node (ref "VT6212") (pin "64") (pinfunction "TESTMODE_64") (pintype "passive"))
    )
    (net (code "168") (name "unconnected-(VT6212-TRDY#-Pad22)") (class "Default")
      (node (ref "VT6212") (pin "22") (pinfunction "TRDY#_22") (pintype "passive"))
    )
    (net (code "169") (name "unconnected-(VT6212-VCC25-Pad4)") (class "Default")
      (node (ref "VT6212") (pin "4") (pinfunction "VCC25_4") (pintype "passive"))
    )
    (net (code "170") (name "unconnected-(VT6212-VCC25-Pad35)") (class "Default")
      (node (ref "VT6212") (pin "35") (pinfunction "VCC25_35") (pintype "passive"))
    )
    (net (code "171") (name "unconnected-(VT6212-VCC25-Pad53)") (class "Default")
      (node (ref "VT6212") (pin "53") (pinfunction "VCC25_53") (pintype "passive"))
    )
    (net (code "172") (name "unconnected-(VT6212-VCC25-Pad115)") (class "Default")
      (node (ref "VT6212") (pin "115") (pinfunction "VCC25_115") (pintype "passive"))
    )
    (net (code "173") (name "unconnected-(VT6212-VCC33-Pad10)") (class "Default")
      (node (ref "VT6212") (pin "10") (pinfunction "VCC33_10") (pintype "passive"))
    )
    (net (code "174") (name "unconnected-(VT6212-VCC33-Pad18)") (class "Default")
      (node (ref "VT6212") (pin "18") (pinfunction "VCC33_18") (pintype "passive"))
    )
    (net (code "175") (name "unconnected-(VT6212-VCC33-Pad26)") (class "Default")
      (node (ref "VT6212") (pin "26") (pinfunction "VCC33_26") (pintype "passive"))
    )
    (net (code "176") (name "unconnected-(VT6212-VCC33-Pad34)") (class "Default")
      (node (ref "VT6212") (pin "34") (pinfunction "VCC33_34") (pintype "passive"))
    )
    (net (code "177") (name "unconnected-(VT6212-VCC33-Pad44)") (class "Default")
      (node (ref "VT6212") (pin "44") (pinfunction "VCC33_44") (pintype "passive"))
    )
    (net (code "178") (name "unconnected-(VT6212-VCC33-Pad52)") (class "Default")
      (node (ref "VT6212") (pin "52") (pinfunction "VCC33_52") (pintype "passive"))
    )
    (net (code "179") (name "unconnected-(VT6212-VCC33-Pad62)") (class "Default")
      (node (ref "VT6212") (pin "62") (pinfunction "VCC33_62") (pintype "passive"))
    )
    (net (code "180") (name "unconnected-(VT6212-VCC33-Pad110)") (class "Default")
      (node (ref "VT6212") (pin "110") (pinfunction "VCC33_110") (pintype "passive"))
    )
    (net (code "181") (name "unconnected-(VT6212-VCC33-Pad120)") (class "Default")
      (node (ref "VT6212") (pin "120") (pinfunction "VCC33_120") (pintype "passive"))
    )
    (net (code "182") (name "unconnected-(VT6212-VCC33-Pad128)") (class "Default")
      (node (ref "VT6212") (pin "128") (pinfunction "VCC33_128") (pintype "passive"))
    )
  )
)
